# ft600.net
KiCad netlist of a schematic drawn in Altium Designer
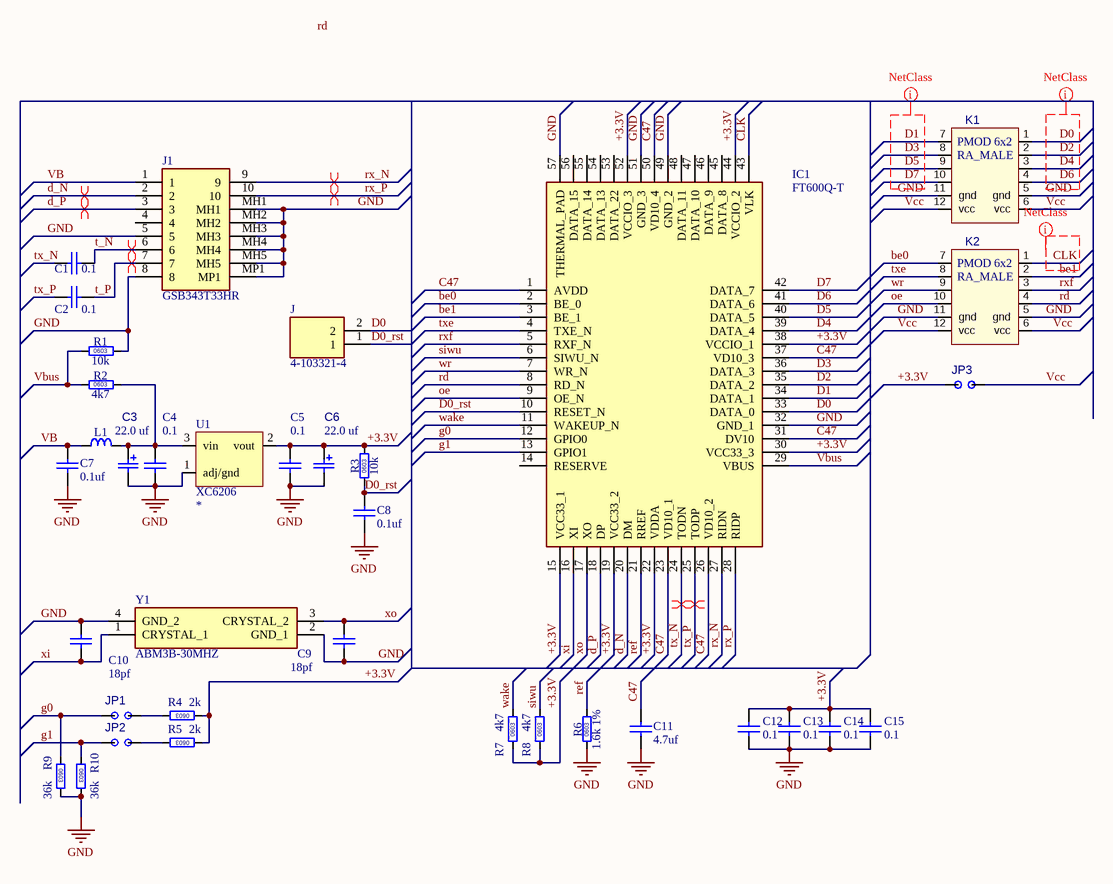
[diagram p0: ft600.SchDoc]

(export (version "E")
  (design (tool "Eeschema 10.0.6"))
  (components
    (comp (ref "C1")
      (value "0.1")
      (footprint "SM0402_3D_cap")
      (description "Capacitor  0402 inch")
      (fields (field (name "Comment") "cap0402") (field (name "PUBLISHER") "Altium Limited"))
      (libsource (lib "alt2017") (part "cap0402"))
    )
    (comp (ref "C2")
      (value "0.1")
      (footprint "SM0402_3D_cap")
      (description "Capacitor  0402 inch")
      (fields (field (name "Comment") "cap0402") (field (name "PUBLISHER") "Altium Limited"))
      (libsource (lib "alt2017") (part "cap0402"))
    )
    (comp (ref "C3")
      (value "CAP_POL_SMA")
      (footprint "CAP_POL_SMA (3216)")
      (description "CAP_POL_SMA(3216)")
      (fields (field (name "ALTIUM_UNNAMED_1") "22.0 uf"))
      (libsource (lib "alt2017") (part "CAP_POL_SMA"))
    )
    (comp (ref "C4")
      (value "0.1")
      (footprint "SM0603 _3D_cap")
      (description "Capacitor  0603 inch")
      (fields (field (name "Comment") "cap0603") (field (name "PUBLISHER") "Altium Limited"))
      (libsource (lib "alt2017") (part "cap0603"))
    )
    (comp (ref "C5")
      (value "0.1")
      (footprint "SM0603 _3D_cap")
      (description "Capacitor  0603 inch")
      (fields (field (name "Comment") "cap0603") (field (name "PUBLISHER") "Altium Limited"))
      (libsource (lib "alt2017") (part "cap0603"))
    )
    (comp (ref "C6")
      (value "CAP_POL_SMA")
      (footprint "CAP_POL_SMA (3216)")
      (description "CAP_POL_SMA(3216)")
      (fields (field (name "ALTIUM_UNNAMED_1") "22.0 uf"))
      (libsource (lib "alt2017") (part "CAP_POL_SMA"))
    )
    (comp (ref "C7")
      (value "0.1uf")
      (footprint "SM0603 _3D_cap")
      (description "Capacitor  0603 inch")
      (fields (field (name "Comment") "cap0603") (field (name "PUBLISHER") "Altium Limited"))
      (libsource (lib "alt2017") (part "cap0603"))
    )
    (comp (ref "C8")
      (value "0.1uf")
      (footprint "SM0603 _3D_cap")
      (description "Capacitor  0603 inch")
      (fields (field (name "Comment") "cap0603") (field (name "PUBLISHER") "Altium Limited"))
      (libsource (lib "alt2017") (part "cap0603"))
    )
    (comp (ref "C9")
      (value "18pf")
      (footprint "SM0603 _3D_cap")
      (description "Capacitor  0603 inch")
      (fields (field (name "Comment") "cap0603") (field (name "PUBLISHER") "Altium Limited"))
      (libsource (lib "alt2017") (part "cap0603"))
    )
    (comp (ref "C10")
      (value "18pf")
      (footprint "SM0603 _3D_cap")
      (description "Capacitor  0603 inch")
      (fields (field (name "Comment") "cap0603") (field (name "PUBLISHER") "Altium Limited"))
      (libsource (lib "alt2017") (part "cap0603"))
    )
    (comp (ref "C11")
      (value "4.7uf")
      (footprint "SM0603 _3D_cap")
      (description "Capacitor  0603 inch")
      (fields (field (name "Comment") "cap0603") (field (name "PUBLISHER") "Altium Limited"))
      (libsource (lib "alt2017") (part "cap0603"))
    )
    (comp (ref "C12")
      (value "0.1")
      (footprint "SM0603 _3D_cap")
      (description "Capacitor  0603 inch")
      (fields (field (name "Comment") "cap0603") (field (name "PUBLISHER") "Altium Limited"))
      (libsource (lib "alt2017") (part "cap0603"))
    )
    (comp (ref "C13")
      (value "0.1")
      (footprint "SM0603 _3D_cap")
      (description "Capacitor  0603 inch")
      (fields (field (name "Comment") "cap0603") (field (name "PUBLISHER") "Altium Limited"))
      (libsource (lib "alt2017") (part "cap0603"))
    )
    (comp (ref "C14")
      (value "0.1")
      (footprint "SM0603 _3D_cap")
      (description "Capacitor  0603 inch")
      (fields (field (name "Comment") "cap0603") (field (name "PUBLISHER") "Altium Limited"))
      (libsource (lib "alt2017") (part "cap0603"))
    )
    (comp (ref "C15")
      (value "0.1")
      (footprint "SM0603 _3D_cap")
      (description "Capacitor  0603 inch")
      (fields (field (name "Comment") "cap0603") (field (name "PUBLISHER") "Altium Limited"))
      (libsource (lib "alt2017") (part "cap0603"))
    )
    (comp (ref "IC1")
      (value "FT600Q-T")
      (footprint "SamacSys:QFN40P700X700X90-57N-D")
      (description "Integrated Circuit")
      (fields (field (name "MOUSER PART NUMBER") "895-FT600Q-T"))
      (libsource (lib "*") (part "FT600Q-T"))
    )
    (comp (ref "J")
      (value "4-103321-4")
      (footprint "TE_4-103321-4")
      (description "Conn Unshrouded Header HDR 2 POS 2.54mm Solder ST Thru-Hole Carton")
      (fields (field (name "DIGI-KEY_PART_NUMBER") "A122847-ND") (field (name "MF") "TE Connectivity"))
      (libsource (lib "4-103321-4") (part "4-103321-4"))
    )
    (comp (ref "J1")
      (value "GSB343T33HR")
      (footprint "SamacSys:GSB343T33HR")
      (description "Connector")
      (fields (field (name "MOUSER PART NUMBER") "523-GSB343T33HR"))
      (libsource (lib "*") (part "GSB343T33HR"))
    )
    (comp (ref "JP1") (value "JUMPER2") (footprint "JUMPER2") (libsource (lib "alt2017") (part "JUMPER2")))
    (comp (ref "JP2") (value "JUMPER2") (footprint "JUMPER2") (libsource (lib "alt2017") (part "JUMPER2")))
    (comp (ref "JP3") (value "JUMPER2") (footprint "JUMPER2") (libsource (lib "alt2017") (part "JUMPER2")))
    (comp (ref "K1")
      (value "PMOD_6x2_ra_male")
      (footprint "PMOD_6x2_right_ANGLE")
      (description "PMOD_6x2_right_angle")
      (libsource (lib "alt2017") (part "PMOD_6x2_ra_male"))
    )
    (comp (ref "K2")
      (value "PMOD_6x2_ra_male")
      (footprint "PMOD_6x2_right_ANGLE")
      (description "PMOD_6x2_right_angle")
      (libsource (lib "alt2017") (part "PMOD_6x2_ra_male"))
    )
    (comp (ref "L1")
      (value "75R@100MHz")
      (footprint "SM0603_3D_res")
      (description "chip inductance 0603")
      (fields
        (field (name "PART NUMBER") "IND0805_MURATA_BLM21BB750SN1D")
        (field (name "POWER") "700mA")
        (field (name "AUTHOR") "S. Jafar")
      )
      (libsource (lib "alt_vovan") (part "chip inductance 0603"))
    )
    (comp (ref "R1")
      (value "10k")
      (footprint "SM0603_3D_res")
      (description "Res_0603_EU")
      (fields
        (field (name "PART NUMBER") "R1206_4K7_1%_0.25W_100PPM")
        (field (name "POWER") "0.25W")
        (field (name "AUTHOR") "CERN DEM JLC")
      )
      (libsource (lib "alt_vovan") (part "Res_0603_EU"))
    )
    (comp (ref "R2")
      (value "4k7")
      (footprint "SM0603_3D_res")
      (description "Res_0603_EU")
      (fields
        (field (name "PART NUMBER") "R1206_4K7_1%_0.25W_100PPM")
        (field (name "POWER") "0.25W")
        (field (name "AUTHOR") "CERN DEM JLC")
      )
      (libsource (lib "alt_vovan") (part "Res_0603_EU"))
    )
    (comp (ref "R3")
      (value "10k")
      (footprint "SM0603_3D_res")
      (description "Res_0603_EU")
      (fields
        (field (name "PART NUMBER") "R1206_4K7_1%_0.25W_100PPM")
        (field (name "POWER") "0.25W")
        (field (name "AUTHOR") "CERN DEM JLC")
      )
      (libsource (lib "alt_vovan") (part "Res_0603_EU"))
    )
    (comp (ref "R4")
      (value "2k")
      (footprint "SM0603_3D_res")
      (description "Res_0603_EU")
      (fields
        (field (name "PART NUMBER") "R1206_4K7_1%_0.25W_100PPM")
        (field (name "POWER") "0.25W")
        (field (name "AUTHOR") "CERN DEM JLC")
      )
      (libsource (lib "alt_vovan") (part "Res_0603_EU"))
    )
    (comp (ref "R5")
      (value "2k")
      (footprint "SM0603_3D_res")
      (description "Res_0603_EU")
      (fields
        (field (name "PART NUMBER") "R1206_4K7_1%_0.25W_100PPM")
        (field (name "POWER") "0.25W")
        (field (name "AUTHOR") "CERN DEM JLC")
      )
      (libsource (lib "alt_vovan") (part "Res_0603_EU"))
    )
    (comp (ref "R6")
      (value "1.6k 1%")
      (footprint "SM0603_3D_res")
      (description "Res_0603_EU")
      (fields
        (field (name "PART NUMBER") "R1206_4K7_1%_0.25W_100PPM")
        (field (name "POWER") "0.25W")
        (field (name "AUTHOR") "CERN DEM JLC")
      )
      (libsource (lib "alt_vovan") (part "Res_0603_EU"))
    )
    (comp (ref "R7")
      (value "4k7")
      (footprint "SM0603_3D_res")
      (description "Res_0603_EU")
      (fields
        (field (name "PART NUMBER") "R1206_4K7_1%_0.25W_100PPM")
        (field (name "POWER") "0.25W")
        (field (name "AUTHOR") "CERN DEM JLC")
      )
      (libsource (lib "alt_vovan") (part "Res_0603_EU"))
    )
    (comp (ref "R8")
      (value "4k7")
      (footprint "SM0603_3D_res")
      (description "Res_0603_EU")
      (fields
        (field (name "PART NUMBER") "R1206_4K7_1%_0.25W_100PPM")
        (field (name "POWER") "0.25W")
        (field (name "AUTHOR") "CERN DEM JLC")
      )
      (libsource (lib "alt_vovan") (part "Res_0603_EU"))
    )
    (comp (ref "R9")
      (value "36k")
      (footprint "SM0603_3D_res")
      (description "Res_0603_EU")
      (fields
        (field (name "PART NUMBER") "R1206_4K7_1%_0.25W_100PPM")
        (field (name "POWER") "0.25W")
        (field (name "AUTHOR") "CERN DEM JLC")
      )
      (libsource (lib "alt_vovan") (part "Res_0603_EU"))
    )
    (comp (ref "R10")
      (value "36k")
      (footprint "SM0603_3D_res")
      (description "Res_0603_EU")
      (fields
        (field (name "PART NUMBER") "R1206_4K7_1%_0.25W_100PPM")
        (field (name "POWER") "0.25W")
        (field (name "AUTHOR") "CERN DEM JLC")
      )
      (libsource (lib "alt_vovan") (part "Res_0603_EU"))
    )
    (comp (ref "U1")
      (value "XC6206")
      (footprint "SOT-23")
      (description "SOT-23-3 ldo")
      (fields (field (name "ALTIUM_UNNAMED_1") "*"))
      (libsource (lib "alt2017") (part "XC6206"))
    )
    (comp (ref "Y1")
      (value "ABM3B-30MHZ")
      (footprint "SamacSys:ABM3B")
      (description "Crystal or Oscillator")
      (fields
        (field (name "MANUFACTURER_PART_NUMBER") "ABM3B-11.0592MHZ-10-1-U-T")
        (field (name "MOUSER PART NUMBER") "815-ABM3B-11.0592-T")
      )
      (libsource (lib "*") (part "ABM3B-11.0592MHZ-10-1-U-T"))
    )
  )
  (nets
    (net (code "1") (name "/+3.3V") (class "Default")
      (node (ref "C12") (pin "2") (pinfunction "2_2") (pintype "passive"))
      (node (ref "C13") (pin "2") (pinfunction "2_2") (pintype "passive"))
      (node (ref "C14") (pin "2") (pinfunction "2_2") (pintype "passive"))
      (node (ref "C15") (pin "2") (pinfunction "2_2") (pintype "passive"))
      (node (ref "C5") (pin "2") (pinfunction "2_2") (pintype "passive"))
      (node (ref "C6") (pin "1") (pinfunction "a_1") (pintype "passive"))
      (node (ref "IC1") (pin "15") (pinfunction "VCC33_1_15") (pintype "passive"))
      (node (ref "IC1") (pin "19") (pinfunction "VCC33_2_19") (pintype "passive"))
      (node (ref "IC1") (pin "22") (pinfunction "VDDA_22") (pintype "passive"))
      (node (ref "IC1") (pin "30") (pinfunction "VCC33_3_30") (pintype "passive"))
      (node (ref "IC1") (pin "38") (pinfunction "VCCIO_1_38") (pintype "passive"))
      (node (ref "IC1") (pin "44") (pinfunction "VCCIO_2_44") (pintype "passive"))
      (node (ref "IC1") (pin "52") (pinfunction "VCCIO_3_52") (pintype "passive"))
      (node (ref "JP3") (pin "2") (pinfunction "2_2") (pintype "passive"))
      (node (ref "R3") (pin "2") (pinfunction "2_2") (pintype "passive"))
      (node (ref "R4") (pin "1") (pinfunction "1_1") (pintype "passive"))
      (node (ref "R5") (pin "1") (pinfunction "1_1") (pintype "passive"))
      (node (ref "R7") (pin "1") (pinfunction "1_1") (pintype "passive"))
      (node (ref "R8") (pin "1") (pinfunction "1_1") (pintype "passive"))
      (node (ref "U1") (pin "2") (pinfunction "vout_2") (pintype "passive"))
    )
    (net (code "2") (name "/C47") (class "Default")
      (node (ref "C11") (pin "2") (pinfunction "2_2") (pintype "passive"))
      (node (ref "IC1") (pin "1") (pinfunction "AVDD_1") (pintype "passive"))
      (node (ref "IC1") (pin "23") (pinfunction "VD10_1_23") (pintype "passive"))
      (node (ref "IC1") (pin "26") (pinfunction "VD10_2_26") (pintype "passive"))
      (node (ref "IC1") (pin "31") (pinfunction "DV10_31") (pintype "passive"))
      (node (ref "IC1") (pin "37") (pinfunction "VD10_3_37") (pintype "passive"))
      (node (ref "IC1") (pin "50") (pinfunction "VD10_4_50") (pintype "passive"))
    )
    (net (code "3") (name "/CLK") (class "Default")
      (node (ref "IC1") (pin "43") (pinfunction "VLK_43") (pintype "passive"))
      (node (ref "K2") (pin "1") (pinfunction "1_1") (pintype "passive"))
    )
    (net (code "4") (name "/D0") (class "Default")
      (node (ref "IC1") (pin "33") (pinfunction "DATA_0_33") (pintype "passive"))
      (node (ref "J") (pin "2") (pinfunction "2_2") (pintype "passive"))
      (node (ref "K1") (pin "1") (pinfunction "1_1") (pintype "passive"))
    )
    (net (code "5") (name "/D0_rst") (class "Default")
      (node (ref "C8") (pin "2") (pinfunction "2_2") (pintype "passive"))
      (node (ref "IC1") (pin "10") (pinfunction "RESET_N_10") (pintype "passive"))
      (node (ref "J") (pin "1") (pinfunction "1_1") (pintype "passive"))
      (node (ref "R3") (pin "1") (pinfunction "1_1") (pintype "passive"))
    )
    (net (code "6") (name "/D1") (class "Default")
      (node (ref "IC1") (pin "34") (pinfunction "DATA_1_34") (pintype "passive"))
      (node (ref "K1") (pin "7") (pinfunction "7_7") (pintype "passive"))
    )
    (net (code "7") (name "/D2") (class "Default")
      (node (ref "IC1") (pin "35") (pinfunction "DATA_2_35") (pintype "passive"))
      (node (ref "K1") (pin "2") (pinfunction "2_2") (pintype "passive"))
    )
    (net (code "8") (name "/D3") (class "Default")
      (node (ref "IC1") (pin "36") (pinfunction "DATA_3_36") (pintype "passive"))
      (node (ref "K1") (pin "8") (pinfunction "8_8") (pintype "passive"))
    )
    (net (code "9") (name "/D4") (class "Default")
      (node (ref "IC1") (pin "39") (pinfunction "DATA_4_39") (pintype "passive"))
      (node (ref "K1") (pin "3") (pinfunction "3_3") (pintype "passive"))
    )
    (net (code "10") (name "/D5") (class "Default")
      (node (ref "IC1") (pin "40") (pinfunction "DATA_5_40") (pintype "passive"))
      (node (ref "K1") (pin "9") (pinfunction "9_9") (pintype "passive"))
    )
    (net (code "11") (name "/D6") (class "Default")
      (node (ref "IC1") (pin "41") (pinfunction "DATA_6_41") (pintype "passive"))
      (node (ref "K1") (pin "4") (pinfunction "4_4") (pintype "passive"))
    )
    (net (code "12") (name "/D7") (class "Default")
      (node (ref "IC1") (pin "42") (pinfunction "DATA_7_42") (pintype "passive"))
      (node (ref "K1") (pin "10") (pinfunction "10_10") (pintype "passive"))
    )
    (net (code "13") (name "/VB") (class "Default")
      (node (ref "C7") (pin "2") (pinfunction "2_2") (pintype "passive"))
      (node (ref "J1") (pin "1") (pinfunction "1_1") (pintype "passive"))
      (node (ref "L1") (pin "1") (pinfunction "1_1") (pintype "passive"))
    )
    (net (code "14") (name "/Vbus") (class "Default")
      (node (ref "IC1") (pin "29") (pinfunction "VBUS_29") (pintype "passive"))
      (node (ref "R1") (pin "1") (pinfunction "1_1") (pintype "passive"))
      (node (ref "R2") (pin "1") (pinfunction "1_1") (pintype "passive"))
    )
    (net (code "15") (name "/Vcc") (class "Default")
      (node (ref "JP3") (pin "1") (pinfunction "1_1") (pintype "passive"))
      (node (ref "K1") (pin "12") (pinfunction "vcc_12") (pintype "passive"))
      (node (ref "K1") (pin "6") (pinfunction "vcc_6") (pintype "passive"))
      (node (ref "K2") (pin "12") (pinfunction "vcc_12") (pintype "passive"))
      (node (ref "K2") (pin "6") (pinfunction "vcc_6") (pintype "passive"))
    )
    (net (code "16") (name "/be0") (class "Default")
      (node (ref "IC1") (pin "2") (pinfunction "BE_0_2") (pintype "passive"))
      (node (ref "K2") (pin "7") (pinfunction "7_7") (pintype "passive"))
    )
    (net (code "17") (name "/be1") (class "Default")
      (node (ref "IC1") (pin "3") (pinfunction "BE_1_3") (pintype "passive"))
      (node (ref "K2") (pin "2") (pinfunction "2_2") (pintype "passive"))
    )
    (net (code "18") (name "/d_N") (class "Default")
      (node (ref "IC1") (pin "20") (pinfunction "DM_20") (pintype "passive"))
      (node (ref "J1") (pin "2") (pinfunction "2_2") (pintype "passive"))
    )
    (net (code "19") (name "/d_P") (class "Default")
      (node (ref "IC1") (pin "18") (pinfunction "DP_18") (pintype "passive"))
      (node (ref "J1") (pin "3") (pinfunction "3_3") (pintype "passive"))
    )
    (net (code "20") (name "/g0") (class "Default")
      (node (ref "IC1") (pin "12") (pinfunction "GPIO0_12") (pintype "passive"))
      (node (ref "JP1") (pin "2") (pinfunction "2_2") (pintype "passive"))
      (node (ref "R9") (pin "1") (pinfunction "1_1") (pintype "passive"))
    )
    (net (code "21") (name "/g1") (class "Default")
      (node (ref "IC1") (pin "13") (pinfunction "GPIO1_13") (pintype "passive"))
      (node (ref "JP2") (pin "2") (pinfunction "2_2") (pintype "passive"))
      (node (ref "R10") (pin "1") (pinfunction "1_1") (pintype "passive"))
    )
    (net (code "22") (name "/oe") (class "Default")
      (node (ref "IC1") (pin "9") (pinfunction "OE_N_9") (pintype "passive"))
      (node (ref "K2") (pin "10") (pinfunction "10_10") (pintype "passive"))
    )
    (net (code "23") (name "/rd") (class "Default")
      (node (ref "IC1") (pin "8") (pinfunction "RD_N_8") (pintype "passive"))
      (node (ref "K2") (pin "4") (pinfunction "4_4") (pintype "passive"))
    )
    (net (code "24") (name "/ref") (class "Default")
      (node (ref "IC1") (pin "21") (pinfunction "RREF_21") (pintype "passive"))
      (node (ref "R6") (pin "2") (pinfunction "2_2") (pintype "passive"))
    )
    (net (code "25") (name "/rx_N") (class "Default")
      (node (ref "IC1") (pin "27") (pinfunction "RIDN_27") (pintype "passive"))
      (node (ref "J1") (pin "9") (pinfunction "9_9") (pintype "passive"))
    )
    (net (code "26") (name "/rx_P") (class "Default")
      (node (ref "IC1") (pin "28") (pinfunction "RIDP_28") (pintype "passive"))
      (node (ref "J1") (pin "10") (pinfunction "10_10") (pintype "passive"))
    )
    (net (code "27") (name "/rxf") (class "Default")
      (node (ref "IC1") (pin "5") (pinfunction "RXF_N_5") (pintype "passive"))
      (node (ref "K2") (pin "3") (pinfunction "3_3") (pintype "passive"))
    )
    (net (code "28") (name "/siwu") (class "Default")
      (node (ref "IC1") (pin "6") (pinfunction "SIWU_N_6") (pintype "passive"))
      (node (ref "R8") (pin "2") (pinfunction "2_2") (pintype "passive"))
    )
    (net (code "29") (name "/t_N") (class "Default")
      (node (ref "C1") (pin "1") (pinfunction "1_1") (pintype "passive"))
      (node (ref "J1") (pin "6") (pinfunction "6_6") (pintype "passive"))
    )
    (net (code "30") (name "/t_P") (class "Default")
      (node (ref "C2") (pin "1") (pinfunction "1_1") (pintype "passive"))
      (node (ref "J1") (pin "7") (pinfunction "7_7") (pintype "passive"))
    )
    (net (code "31") (name "/tx_N") (class "Default")
      (node (ref "C1") (pin "2") (pinfunction "2_2") (pintype "passive"))
      (node (ref "IC1") (pin "24") (pinfunction "TODN_24") (pintype "passive"))
    )
    (net (code "32") (name "/tx_P") (class "Default")
      (node (ref "C2") (pin "2") (pinfunction "2_2") (pintype "passive"))
      (node (ref "IC1") (pin "25") (pinfunction "TODP_25") (pintype "passive"))
    )
    (net (code "33") (name "/txe") (class "Default")
      (node (ref "IC1") (pin "4") (pinfunction "TXE_N_4") (pintype "passive"))
      (node (ref "K2") (pin "8") (pinfunction "8_8") (pintype "passive"))
    )
    (net (code "34") (name "/wake") (class "Default")
      (node (ref "IC1") (pin "11") (pinfunction "WAKEUP_N_11") (pintype "passive"))
      (node (ref "R7") (pin "2") (pinfunction "2_2") (pintype "passive"))
    )
    (net (code "35") (name "/wr") (class "Default")
      (node (ref "IC1") (pin "7") (pinfunction "WR_N_7") (pintype "passive"))
      (node (ref "K2") (pin "9") (pinfunction "9_9") (pintype "passive"))
    )
    (net (code "36") (name "/xi") (class "Default")
      (node (ref "C10") (pin "1") (pinfunction "1_1") (pintype "passive"))
      (node (ref "IC1") (pin "16") (pinfunction "XI_16") (pintype "passive"))
      (node (ref "Y1") (pin "1") (pinfunction "CRYSTAL_1_1") (pintype "passive"))
    )
    (net (code "37") (name "/xo") (class "Default")
      (node (ref "C9") (pin "2") (pinfunction "2_2") (pintype "passive"))
      (node (ref "IC1") (pin "17") (pinfunction "XO_17") (pintype "passive"))
      (node (ref "Y1") (pin "3") (pinfunction "CRYSTAL_2_3") (pintype "passive"))
    )
    (net (code "38") (name "GND") (class "Default")
      (node (ref "C10") (pin "2") (pinfunction "2_2") (pintype "passive"))
      (node (ref "C11") (pin "1") (pinfunction "1_1") (pintype "passive"))
      (node (ref "C12") (pin "1") (pinfunction "1_1") (pintype "passive"))
      (node (ref "C13") (pin "1") (pinfunction "1_1") (pintype "passive"))
      (node (ref "C14") (pin "1") (pinfunction "1_1") (pintype "passive"))
      (node (ref "C15") (pin "1") (pinfunction "1_1") (pintype "passive"))
      (node (ref "C3") (pin "2") (pinfunction "b_2") (pintype "passive"))
      (node (ref "C4") (pin "1") (pinfunction "1_1") (pintype "passive"))
      (node (ref "C5") (pin "1") (pinfunction "1_1") (pintype "passive"))
      (node (ref "C6") (pin "2") (pinfunction "b_2") (pintype "passive"))
      (node (ref "C7") (pin "1") (pinfunction "1_1") (pintype "passive"))
      (node (ref "C8") (pin "1") (pinfunction "1_1") (pintype "passive"))
      (node (ref "C9") (pin "1") (pinfunction "1_1") (pintype "passive"))
      (node (ref "IC1") (pin "32") (pinfunction "GND_1_32") (pintype "passive"))
      (node (ref "IC1") (pin "49") (pinfunction "GND_2_49") (pintype "passive"))
      (node (ref "IC1") (pin "51") (pinfunction "GND_3_51") (pintype "passive"))
      (node (ref "IC1") (pin "57") (pinfunction "THERMAL_PAD_57") (pintype "passive"))
      (node (ref "J1") (pin "5") (pinfunction "5_5") (pintype "passive"))
      (node (ref "J1") (pin "8") (pinfunction "8_8") (pintype "passive"))
      (node (ref "J1") (pin "MH1") (pinfunction "MH1_MH1") (pintype "passive"))
      (node (ref "J1") (pin "MH2") (pinfunction "MH2_MH2") (pintype "passive"))
      (node (ref "J1") (pin "MH3") (pinfunction "MH3_MH3") (pintype "passive"))
      (node (ref "J1") (pin "MH4") (pinfunction "MH4_MH4") (pintype "passive"))
      (node (ref "J1") (pin "MH5") (pinfunction "MH5_MH5") (pintype "passive"))
      (node (ref "J1") (pin "MP1") (pinfunction "MP1_MP1") (pintype "passive"))
      (node (ref "K1") (pin "11") (pinfunction "gnd_11") (pintype "passive"))
      (node (ref "K1") (pin "5") (pinfunction "gnd_5") (pintype "passive"))
      (node (ref "K2") (pin "11") (pinfunction "gnd_11") (pintype "passive"))
      (node (ref "K2") (pin "5") (pinfunction "gnd_5") (pintype "passive"))
      (node (ref "R1") (pin "2") (pinfunction "2_2") (pintype "passive"))
      (node (ref "R10") (pin "2") (pinfunction "2_2") (pintype "passive"))
      (node (ref "R6") (pin "1") (pinfunction "1_1") (pintype "passive"))
      (node (ref "R9") (pin "2") (pinfunction "2_2") (pintype "passive"))
      (node (ref "U1") (pin "1") (pinfunction "adj/gnd_1") (pintype "passive"))
      (node (ref "Y1") (pin "2") (pinfunction "GND_1_2") (pintype "passive"))
      (node (ref "Y1") (pin "4") (pinfunction "GND_2_4") (pintype "passive"))
    )
    (net (code "39") (name "Net-(C3-a)") (class "Default")
      (node (ref "C3") (pin "1") (pinfunction "a_1") (pintype "passive"))
      (node (ref "C4") (pin "2") (pinfunction "2_2") (pintype "passive"))
      (node (ref "L1") (pin "2") (pinfunction "2_2") (pintype "passive"))
      (node (ref "R2") (pin "2") (pinfunction "2_2") (pintype "passive"))
      (node (ref "U1") (pin "3") (pinfunction "vin_3") (pintype "passive"))
    )
    (net (code "40") (name "Net-(JP1-Pad1)") (class "Default")
      (node (ref "JP1") (pin "1") (pinfunction "1_1") (pintype "passive"))
      (node (ref "R4") (pin "2") (pinfunction "2_2") (pintype "passive"))
    )
    (net (code "41") (name "Net-(JP2-Pad1)") (class "Default")
      (node (ref "JP2") (pin "1") (pinfunction "1_1") (pintype "passive"))
      (node (ref "R5") (pin "2") (pinfunction "2_2") (pintype "passive"))
    )
    (net (code "42") (name "unconnected-(IC1-DATA_8-Pad45)") (class "Default")
      (node (ref "IC1") (pin "45") (pinfunction "DATA_8_45") (pintype "passive"))
    )
    (net (code "43") (name "unconnected-(IC1-DATA_9-Pad46)") (class "Default")
      (node (ref "IC1") (pin "46") (pinfunction "DATA_9_46") (pintype "passive"))
    )
    (net (code "44") (name "unconnected-(IC1-DATA_10-Pad47)") (class "Default")
      (node (ref "IC1") (pin "47") (pinfunction "DATA_10_47") (pintype "passive"))
    )
    (net (code "45") (name "unconnected-(IC1-DATA_11-Pad48)") (class "Default")
      (node (ref "IC1") (pin "48") (pinfunction "DATA_11_48") (pintype "passive"))
    )
    (net (code "46") (name "unconnected-(IC1-DATA_13-Pad54)") (class "Default")
      (node (ref "IC1") (pin "54") (pinfunction "DATA_13_54") (pintype "passive"))
    )
    (net (code "47") (name "unconnected-(IC1-DATA_14-Pad55)") (class "Default")
      (node (ref "IC1") (pin "55") (pinfunction "DATA_14_55") (pintype "passive"))
    )
    (net (code "48") (name "unconnected-(IC1-DATA_15-Pad56)") (class "Default")
      (node (ref "IC1") (pin "56") (pinfunction "DATA_15_56") (pintype "passive"))
    )
    (net (code "49") (name "unconnected-(IC1-DATA_22-Pad53)") (class "Default")
      (node (ref "IC1") (pin "53") (pinfunction "DATA_22_53") (pintype "passive"))
    )
    (net (code "50") (name "unconnected-(IC1-RESERVE-Pad14)") (class "Default")
      (node (ref "IC1") (pin "14") (pinfunction "RESERVE_14") (pintype "passive"))
    )
    (net (code "51") (name "unconnected-(J1-Pad4)") (class "Default")
      (node (ref "J1") (pin "4") (pinfunction "4_4") (pintype "passive"))
    )
  )
)
